# Keyboard.net
KiCad netlist of a schematic drawn in Altium Designer
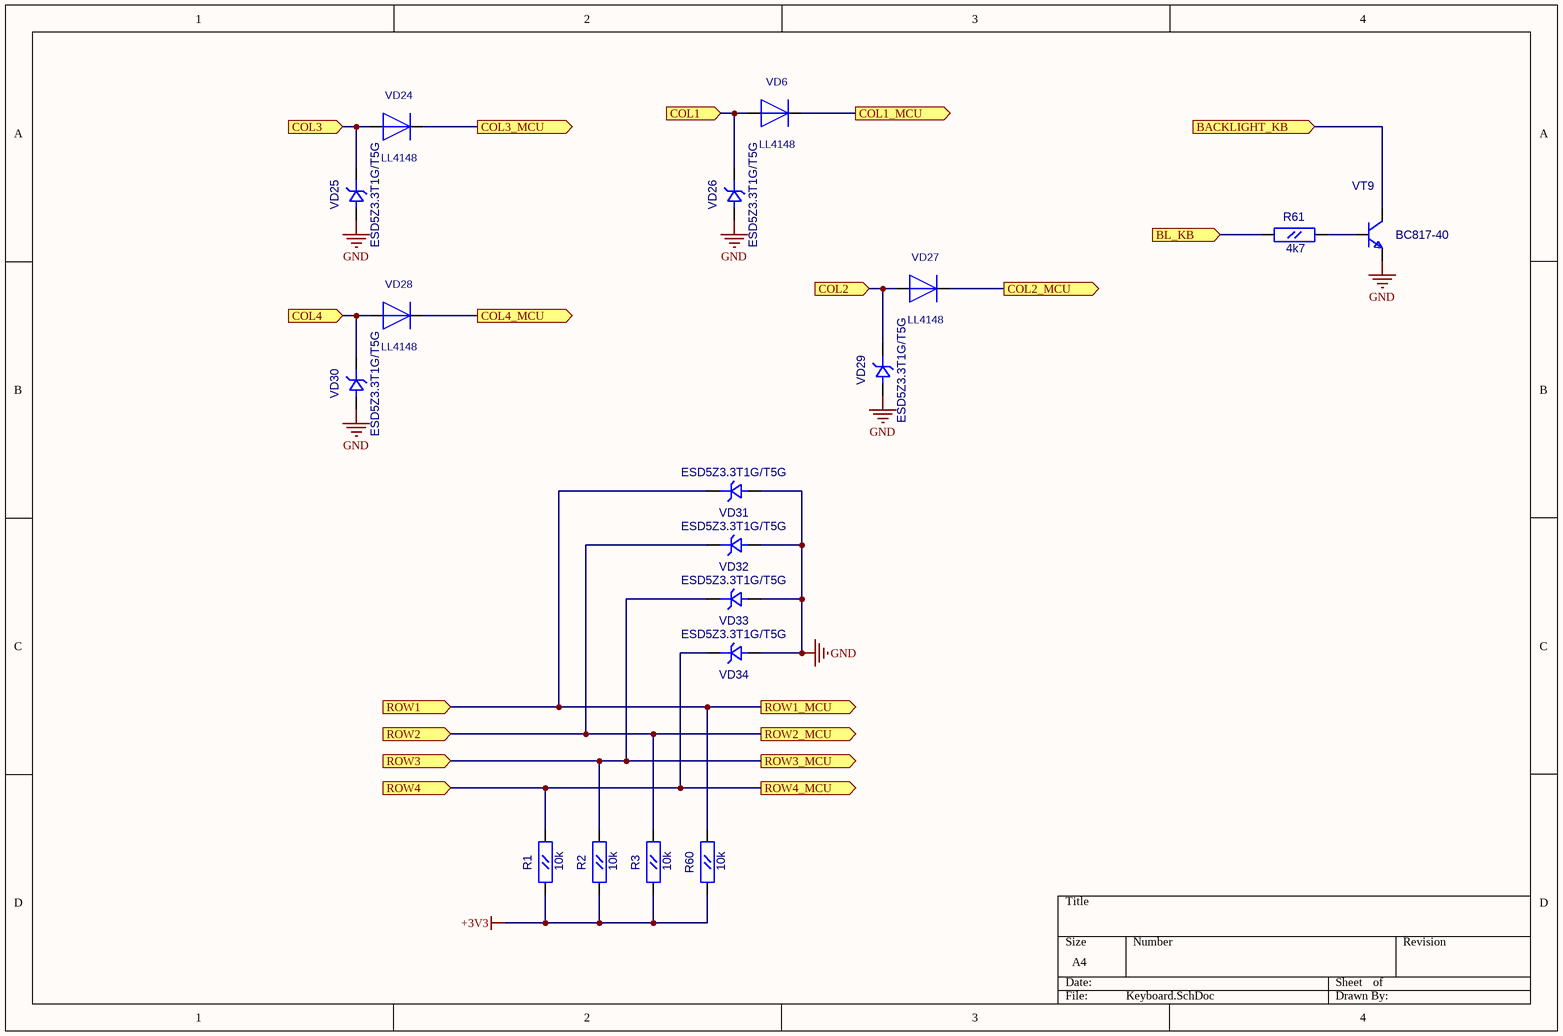
[diagram p0: Keyboard.SchDoc]

(export (version "E")
  (design (tool "Eeschema 10.0.6"))
  (components
    (comp (ref "R1")
      (value "10k")
      (footprint "RC0603")
      (description "RC0603")
      (libsource (lib "gprs_modem_2") (part "RC0603"))
    )
    (comp (ref "R2")
      (value "10k")
      (footprint "RC0603")
      (description "RC0603")
      (libsource (lib "gprs_modem_2") (part "RC0603"))
    )
    (comp (ref "R3")
      (value "10k")
      (footprint "RC0603")
      (description "RC0603")
      (libsource (lib "gprs_modem_2") (part "RC0603"))
    )
    (comp (ref "R60")
      (value "10k")
      (footprint "RC0603")
      (description "RC0603")
      (libsource (lib "gprs_modem_2") (part "RC0603"))
    )
    (comp (ref "R61")
      (value "4k7")
      (footprint "RC0603")
      (description "RC0603")
      (libsource (lib "gprs_modem_2") (part "RC0603"))
    )
    (comp (ref "VD6") (value "LL4148") (footprint "SOD-80") (libsource (lib "gprs_modem_2") (part "LL4148")))
    (comp (ref "VD24") (value "LL4148") (footprint "SOD-80") (libsource (lib "gprs_modem_2") (part "LL4148")))
    (comp (ref "VD25")
      (value "ESD5Z3.3T1G/T5G")
      (footprint "SOD-523")
      (description "Supressor")
      (libsource (lib "gprs_modem_2") (part "ESD5Z"))
    )
    (comp (ref "VD26")
      (value "ESD5Z3.3T1G/T5G")
      (footprint "SOD-523")
      (description "Supressor")
      (libsource (lib "gprs_modem_2") (part "ESD5Z"))
    )
    (comp (ref "VD27") (value "LL4148") (footprint "SOD-80") (libsource (lib "gprs_modem_2") (part "LL4148")))
    (comp (ref "VD28") (value "LL4148") (footprint "SOD-80") (libsource (lib "gprs_modem_2") (part "LL4148")))
    (comp (ref "VD29")
      (value "ESD5Z3.3T1G/T5G")
      (footprint "SOD-523")
      (description "Supressor")
      (libsource (lib "gprs_modem_2") (part "ESD5Z"))
    )
    (comp (ref "VD30")
      (value "ESD5Z3.3T1G/T5G")
      (footprint "SOD-523")
      (description "Supressor")
      (libsource (lib "gprs_modem_2") (part "ESD5Z"))
    )
    (comp (ref "VD31")
      (value "ESD5Z3.3T1G/T5G")
      (footprint "SOD-523")
      (description "Supressor")
      (libsource (lib "gprs_modem_2") (part "ESD5Z"))
    )
    (comp (ref "VD32")
      (value "ESD5Z3.3T1G/T5G")
      (footprint "SOD-523")
      (description "Supressor")
      (libsource (lib "gprs_modem_2") (part "ESD5Z"))
    )
    (comp (ref "VD33")
      (value "ESD5Z3.3T1G/T5G")
      (footprint "SOD-523")
      (description "Supressor")
      (libsource (lib "gprs_modem_2") (part "ESD5Z"))
    )
    (comp (ref "VD34")
      (value "ESD5Z3.3T1G/T5G")
      (footprint "SOD-523")
      (description "Supressor")
      (libsource (lib "gprs_modem_2") (part "ESD5Z"))
    )
    (comp (ref "VT9")
      (value "BC817-40")
      (footprint "SOT-23(123)")
      (description "NPN 500ma transistor")
      (libsource (lib "gprs_modem_2") (part "BC846BLT1"))
    )
  )
  (nets
    (net (code "1") (name "+3V3") (class "Default")
      (node (ref "R1") (pin "1") (pinfunction "A_1") (pintype "passive"))
      (node (ref "R2") (pin "1") (pinfunction "A_1") (pintype "passive"))
      (node (ref "R3") (pin "1") (pinfunction "A_1") (pintype "passive"))
      (node (ref "R60") (pin "1") (pinfunction "A_1") (pintype "passive"))
    )
    (net (code "2") (name "/BACKLIGHT_KB") (class "Default")
      (node (ref "VT9") (pin "3") (pinfunction "C_3") (pintype "passive"))
    )
    (net (code "3") (name "/BL_KB") (class "Default")
      (node (ref "R61") (pin "1") (pinfunction "A_1") (pintype "passive"))
    )
    (net (code "4") (name "/COL1") (class "Default")
      (node (ref "VD26") (pin "2") (pinfunction "K_2") (pintype "passive"))
      (node (ref "VD6") (pin "1") (pinfunction "-_1") (pintype "passive"))
    )
    (net (code "5") (name "/COL1_MCU") (class "Default")
      (node (ref "VD6") (pin "2") (pinfunction "+_2") (pintype "passive"))
    )
    (net (code "6") (name "/COL2") (class "Default")
      (node (ref "VD27") (pin "1") (pinfunction "-_1") (pintype "passive"))
      (node (ref "VD29") (pin "2") (pinfunction "K_2") (pintype "passive"))
    )
    (net (code "7") (name "/COL2_MCU") (class "Default")
      (node (ref "VD27") (pin "2") (pinfunction "+_2") (pintype "passive"))
    )
    (net (code "8") (name "/COL3") (class "Default")
      (node (ref "VD24") (pin "1") (pinfunction "-_1") (pintype "passive"))
      (node (ref "VD25") (pin "2") (pinfunction "K_2") (pintype "passive"))
    )
    (net (code "9") (name "/COL3_MCU") (class "Default")
      (node (ref "VD24") (pin "2") (pinfunction "+_2") (pintype "passive"))
    )
    (net (code "10") (name "/COL4") (class "Default")
      (node (ref "VD28") (pin "1") (pinfunction "-_1") (pintype "passive"))
      (node (ref "VD30") (pin "2") (pinfunction "K_2") (pintype "passive"))
    )
    (net (code "11") (name "/COL4_MCU") (class "Default")
      (node (ref "VD28") (pin "2") (pinfunction "+_2") (pintype "passive"))
    )
    (net (code "12") (name "/ROW1") (class "Default")
      (node (ref "R60") (pin "2") (pinfunction "B_2") (pintype "passive"))
      (node (ref "VD31") (pin "2") (pinfunction "K_2") (pintype "passive"))
    )
    (net (code "13") (name "/ROW2") (class "Default")
      (node (ref "R3") (pin "2") (pinfunction "B_2") (pintype "passive"))
      (node (ref "VD32") (pin "2") (pinfunction "K_2") (pintype "passive"))
    )
    (net (code "14") (name "/ROW3") (class "Default")
      (node (ref "R2") (pin "2") (pinfunction "B_2") (pintype "passive"))
      (node (ref "VD33") (pin "2") (pinfunction "K_2") (pintype "passive"))
    )
    (net (code "15") (name "/ROW4") (class "Default")
      (node (ref "R1") (pin "2") (pinfunction "B_2") (pintype "passive"))
      (node (ref "VD34") (pin "2") (pinfunction "K_2") (pintype "passive"))
    )
    (net (code "16") (name "GND") (class "Default")
      (node (ref "VD25") (pin "1") (pinfunction "A_1") (pintype "passive"))
      (node (ref "VD26") (pin "1") (pinfunction "A_1") (pintype "passive"))
      (node (ref "VD29") (pin "1") (pinfunction "A_1") (pintype "passive"))
      (node (ref "VD30") (pin "1") (pinfunction "A_1") (pintype "passive"))
      (node (ref "VD31") (pin "1") (pinfunction "A_1") (pintype "passive"))
      (node (ref "VD32") (pin "1") (pinfunction "A_1") (pintype "passive"))
      (node (ref "VD33") (pin "1") (pinfunction "A_1") (pintype "passive"))
      (node (ref "VD34") (pin "1") (pinfunction "A_1") (pintype "passive"))
      (node (ref "VT9") (pin "2") (pinfunction "E_2") (pintype "passive"))
    )
    (net (code "17") (name "Net-(R61-B)") (class "Default")
      (node (ref "R61") (pin "2") (pinfunction "B_2") (pintype "passive"))
      (node (ref "VT9") (pin "1") (pinfunction "B_1") (pintype "passive"))
    )
  )
)
